# Power_MPU.net
KiCad netlist of a schematic drawn in Altium Designer
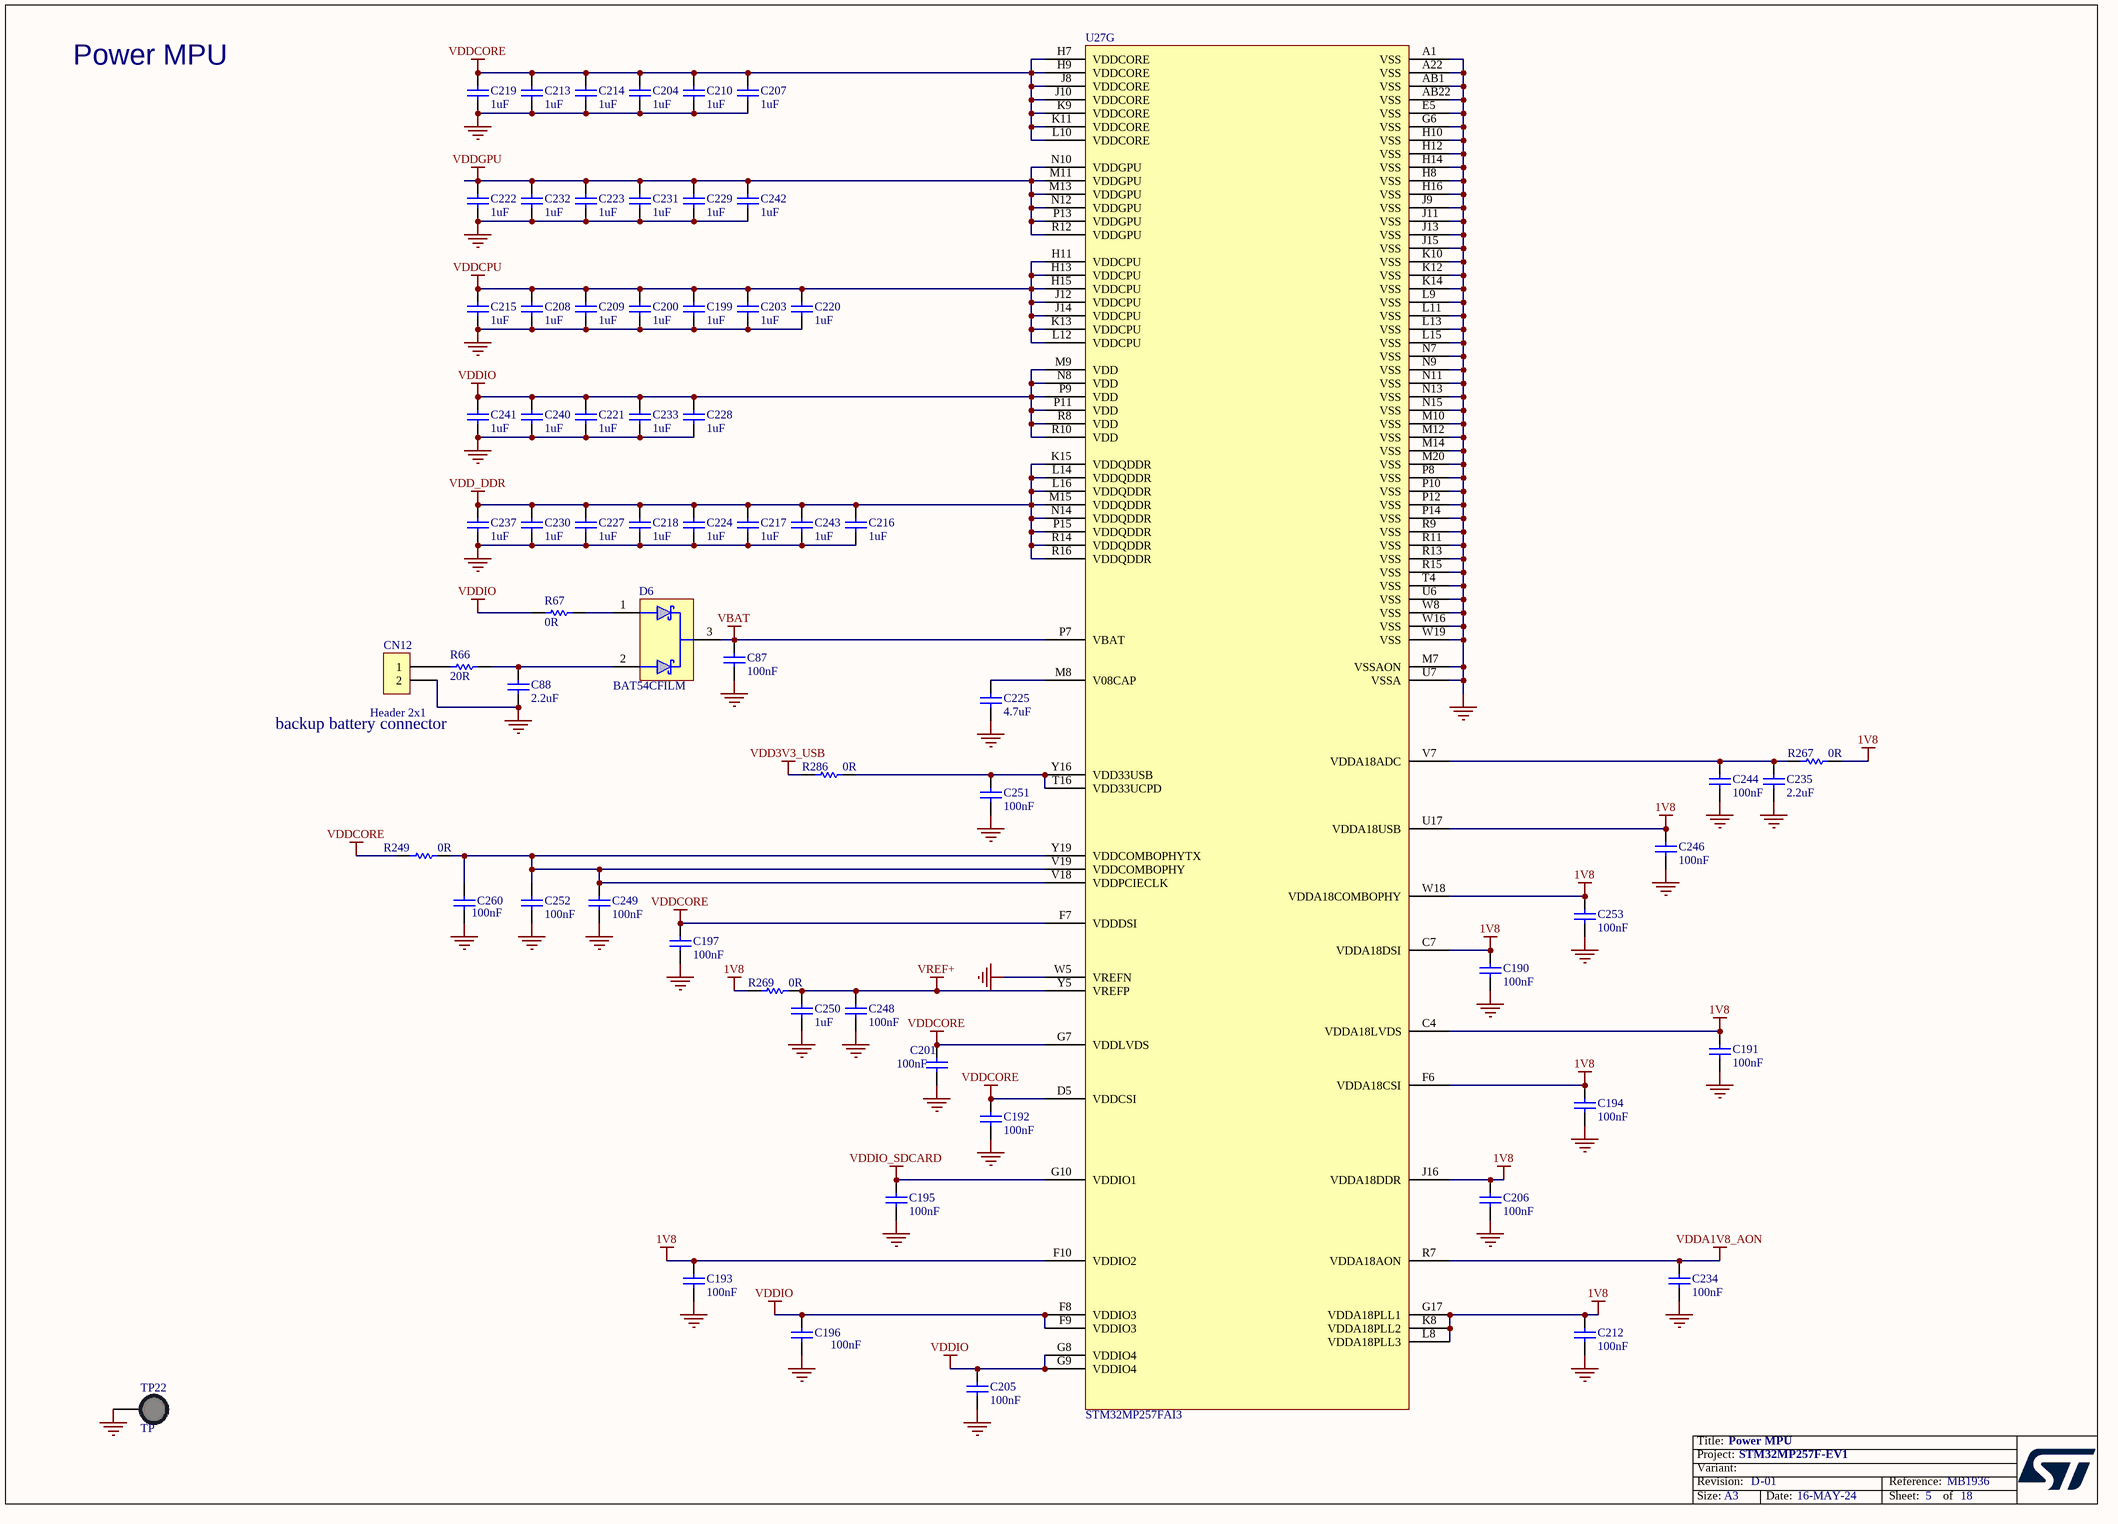
[diagram p0: Power_MPU.SchDoc]

(export (version "E")
  (design (tool "Eeschema 10.0.6"))
  (components
    (comp (ref "C87")
      (value "100nF")
      (footprint "MCD_PARTS:C0402")
      (description "Capacitor,100nF,16V,X7R,10%,0402")
      (fields
        (field (name "INTERNAL_PART_NUMBER") "MCD-00006")
        (field (name "MANUFACTURER_PART_NUMBER") "CC0402KRX7R7BB104")
        (field (name "PROVIDED_BY") "SUBCO")
      )
      (libsource (lib "MCD_PARTS_database") (part "Capacitor"))
    )
    (comp (ref "C88")
      (value "2.2uF")
      (footprint "MCD_PARTS:C0402")
      (description "Capacitor, MLCC, 2.2uF, 6V3, X5R,+/-10%, 0402, T=0.5mm")
      (fields (field (name "INTERNAL_PART_NUMBER") "MCD-01823") (field (name "MANUFACTURER") "MURATA"))
      (libsource (lib "MCD_PARTS_database") (part "Capacitor"))
    )
    (comp (ref "C190")
      (value "100nF")
      (footprint "MCD_PARTS:C0201_MURATA_GRM033_H0P3")
      (description "Capacitor, MLCC,100nF, 10V, X7R, +/-10%, 0201, T=0.3mm")
      (fields (field (name "INTERNAL_PART_NUMBER") "MCD-01535") (field (name "MANUFACTURER") "MURATA"))
      (libsource (lib "MCD_PARTS_database") (part "Capacitor"))
    )
    (comp (ref "C191")
      (value "100nF")
      (footprint "MCD_PARTS:C0201_MURATA_GRM033_H0P3")
      (description "Capacitor, MLCC,100nF, 10V, X7R, +/-10%, 0201, T=0.3mm")
      (fields (field (name "INTERNAL_PART_NUMBER") "MCD-01535") (field (name "MANUFACTURER") "MURATA"))
      (libsource (lib "MCD_PARTS_database") (part "Capacitor"))
    )
    (comp (ref "C192")
      (value "100nF")
      (footprint "MCD_PARTS:C0201_MURATA_GRM033_H0P3")
      (description "Capacitor, MLCC,100nF, 10V, X7R, +/-10%, 0201, T=0.3mm")
      (fields (field (name "INTERNAL_PART_NUMBER") "MCD-01535") (field (name "MANUFACTURER") "MURATA"))
      (libsource (lib "MCD_PARTS_database") (part "Capacitor"))
    )
    (comp (ref "C193")
      (value "100nF")
      (footprint "MCD_PARTS:C0201_MURATA_GRM033_H0P3")
      (description "Capacitor, MLCC,100nF, 10V, X7R, +/-10%, 0201, T=0.3mm")
      (fields (field (name "INTERNAL_PART_NUMBER") "MCD-01535") (field (name "MANUFACTURER") "MURATA"))
      (libsource (lib "MCD_PARTS_database") (part "Capacitor"))
    )
    (comp (ref "C194")
      (value "100nF")
      (footprint "MCD_PARTS:C0201_MURATA_GRM033_H0P3")
      (description "Capacitor, MLCC,100nF, 10V, X7R, +/-10%, 0201, T=0.3mm")
      (fields (field (name "INTERNAL_PART_NUMBER") "MCD-01535") (field (name "MANUFACTURER") "MURATA"))
      (libsource (lib "MCD_PARTS_database") (part "Capacitor"))
    )
    (comp (ref "C195")
      (value "100nF")
      (footprint "MCD_PARTS:C0201_MURATA_GRM033_H0P3")
      (description "Capacitor, MLCC,100nF, 10V, X7R, +/-10%, 0201, T=0.3mm")
      (fields (field (name "INTERNAL_PART_NUMBER") "MCD-01535") (field (name "MANUFACTURER") "MURATA"))
      (libsource (lib "MCD_PARTS_database") (part "Capacitor"))
    )
    (comp (ref "C196")
      (value "100nF")
      (footprint "MCD_PARTS:C0201_MURATA_GRM033_H0P3")
      (description "Capacitor, MLCC,100nF, 10V, X7R, +/-10%, 0201, T=0.3mm")
      (fields (field (name "INTERNAL_PART_NUMBER") "MCD-01535") (field (name "MANUFACTURER") "MURATA"))
      (libsource (lib "MCD_PARTS_database") (part "Capacitor"))
    )
    (comp (ref "C197")
      (value "100nF")
      (footprint "MCD_PARTS:C0201_MURATA_GRM033_H0P3")
      (description "Capacitor, MLCC,100nF, 10V, X7R, +/-10%, 0201, T=0.3mm")
      (fields (field (name "INTERNAL_PART_NUMBER") "MCD-01535") (field (name "MANUFACTURER") "MURATA"))
      (libsource (lib "MCD_PARTS_database") (part "Capacitor"))
    )
    (comp (ref "C199")
      (value "1uF")
      (footprint "MCD_PARTS:C0201_MURATA_GRM033_H0P3")
      (description "Capacitor, MLCC, 1uF, 6.3V, X5R, +/-20%, 0201, T=0,3mm")
      (fields
        (field (name "INTERNAL_PART_NUMBER") "MCD-02377")
        (field (name "MANUFACTURER_PART_NUMBER") "GRM033R60J105MEA2")
      )
      (libsource (lib "MCD_PARTS_database") (part "Capacitor"))
    )
    (comp (ref "C200")
      (value "1uF")
      (footprint "MCD_PARTS:C0201_MURATA_GRM033_H0P3")
      (description "Capacitor, MLCC, 1uF, 6.3V, X5R, +/-20%, 0201, T=0,3mm")
      (fields
        (field (name "INTERNAL_PART_NUMBER") "MCD-02377")
        (field (name "MANUFACTURER_PART_NUMBER") "GRM033R60J105MEA2")
      )
      (libsource (lib "MCD_PARTS_database") (part "Capacitor"))
    )
    (comp (ref "C201")
      (value "100nF")
      (footprint "MCD_PARTS:C0201_MURATA_GRM033_H0P3")
      (description "Capacitor, MLCC,100nF, 10V, X7R, +/-10%, 0201, T=0.3mm")
      (fields (field (name "INTERNAL_PART_NUMBER") "MCD-01535") (field (name "MANUFACTURER") "MURATA"))
      (libsource (lib "MCD_PARTS_database") (part "Capacitor"))
    )
    (comp (ref "C203")
      (value "1uF")
      (footprint "MCD_PARTS:C0201_MURATA_GRM033_H0P3")
      (description "Capacitor, MLCC, 1uF, 6.3V, X5R, +/-20%, 0201, T=0,3mm")
      (fields
        (field (name "INTERNAL_PART_NUMBER") "MCD-02377")
        (field (name "MANUFACTURER_PART_NUMBER") "GRM033R60J105MEA2")
      )
      (libsource (lib "MCD_PARTS_database") (part "Capacitor"))
    )
    (comp (ref "C204")
      (value "1uF")
      (footprint "MCD_PARTS:C0201_MURATA_GRM033_H0P3")
      (description "Capacitor, MLCC, 1uF, 6.3V, X5R, +/-20%, 0201, T=0,3mm")
      (fields
        (field (name "INTERNAL_PART_NUMBER") "MCD-02377")
        (field (name "MANUFACTURER_PART_NUMBER") "GRM033R60J105MEA2")
      )
      (libsource (lib "MCD_PARTS_database") (part "Capacitor"))
    )
    (comp (ref "C205")
      (value "100nF")
      (footprint "MCD_PARTS:C0201_MURATA_GRM033_H0P3")
      (description "Capacitor, MLCC,100nF, 10V, X7R, +/-10%, 0201, T=0.3mm")
      (fields (field (name "INTERNAL_PART_NUMBER") "MCD-01535") (field (name "MANUFACTURER") "MURATA"))
      (libsource (lib "MCD_PARTS_database") (part "Capacitor"))
    )
    (comp (ref "C206")
      (value "100nF")
      (footprint "MCD_PARTS:C0201_MURATA_GRM033_H0P3")
      (description "Capacitor, MLCC,100nF, 10V, X7R, +/-10%, 0201, T=0.3mm")
      (fields (field (name "INTERNAL_PART_NUMBER") "MCD-01535") (field (name "MANUFACTURER") "MURATA"))
      (libsource (lib "MCD_PARTS_database") (part "Capacitor"))
    )
    (comp (ref "C207")
      (value "1uF")
      (footprint "MCD_PARTS:C0201_MURATA_GRM033_H0P3")
      (description "Capacitor, MLCC, 1uF, 6.3V, X5R, +/-20%, 0201, T=0,3mm")
      (fields
        (field (name "INTERNAL_PART_NUMBER") "MCD-02377")
        (field (name "MANUFACTURER_PART_NUMBER") "GRM033R60J105MEA2")
      )
      (libsource (lib "MCD_PARTS_database") (part "Capacitor"))
    )
    (comp (ref "C208")
      (value "1uF")
      (footprint "MCD_PARTS:C0201_MURATA_GRM033_H0P3")
      (description "Capacitor, MLCC, 1uF, 6.3V, X5R, +/-20%, 0201, T=0,3mm")
      (fields
        (field (name "INTERNAL_PART_NUMBER") "MCD-02377")
        (field (name "MANUFACTURER_PART_NUMBER") "GRM033R60J105MEA2")
      )
      (libsource (lib "MCD_PARTS_database") (part "Capacitor"))
    )
    (comp (ref "C209")
      (value "1uF")
      (footprint "MCD_PARTS:C0201_MURATA_GRM033_H0P3")
      (description "Capacitor, MLCC, 1uF, 6.3V, X5R, +/-20%, 0201, T=0,3mm")
      (fields
        (field (name "INTERNAL_PART_NUMBER") "MCD-02377")
        (field (name "MANUFACTURER_PART_NUMBER") "GRM033R60J105MEA2")
      )
      (libsource (lib "MCD_PARTS_database") (part "Capacitor"))
    )
    (comp (ref "C210")
      (value "1uF")
      (footprint "MCD_PARTS:C0201_MURATA_GRM033_H0P3")
      (description "Capacitor, MLCC, 1uF, 6.3V, X5R, +/-20%, 0201, T=0,3mm")
      (fields
        (field (name "INTERNAL_PART_NUMBER") "MCD-02377")
        (field (name "MANUFACTURER_PART_NUMBER") "GRM033R60J105MEA2")
      )
      (libsource (lib "MCD_PARTS_database") (part "Capacitor"))
    )
    (comp (ref "C212")
      (value "100nF")
      (footprint "MCD_PARTS:C0201_MURATA_GRM033_H0P3")
      (description "Capacitor, MLCC,100nF, 10V, X7R, +/-10%, 0201, T=0.3mm")
      (fields (field (name "INTERNAL_PART_NUMBER") "MCD-01535") (field (name "MANUFACTURER") "MURATA"))
      (libsource (lib "MCD_PARTS_database") (part "Capacitor"))
    )
    (comp (ref "C213")
      (value "1uF")
      (footprint "MCD_PARTS:C0201_MURATA_GRM033_H0P3")
      (description "Capacitor, MLCC, 1uF, 6.3V, X5R, +/-20%, 0201, T=0,3mm")
      (fields
        (field (name "INTERNAL_PART_NUMBER") "MCD-02377")
        (field (name "MANUFACTURER_PART_NUMBER") "GRM033R60J105MEA2")
      )
      (libsource (lib "MCD_PARTS_database") (part "Capacitor"))
    )
    (comp (ref "C214")
      (value "1uF")
      (footprint "MCD_PARTS:C0201_MURATA_GRM033_H0P3")
      (description "Capacitor, MLCC, 1uF, 6.3V, X5R, +/-20%, 0201, T=0,3mm")
      (fields
        (field (name "INTERNAL_PART_NUMBER") "MCD-02377")
        (field (name "MANUFACTURER_PART_NUMBER") "GRM033R60J105MEA2")
      )
      (libsource (lib "MCD_PARTS_database") (part "Capacitor"))
    )
    (comp (ref "C215")
      (value "1uF")
      (footprint "MCD_PARTS:C0201_MURATA_GRM033_H0P3")
      (description "Capacitor, MLCC, 1uF, 6.3V, X5R, +/-20%, 0201, T=0,3mm")
      (fields
        (field (name "INTERNAL_PART_NUMBER") "MCD-02377")
        (field (name "MANUFACTURER_PART_NUMBER") "GRM033R60J105MEA2")
      )
      (libsource (lib "MCD_PARTS_database") (part "Capacitor"))
    )
    (comp (ref "C216")
      (value "1uF")
      (footprint "MCD_PARTS:C0201_MURATA_GRM033_H0P3")
      (description "Capacitor, MLCC, 1uF, 6.3V, X5R, +/-20%, 0201, T=0,3mm")
      (fields
        (field (name "INTERNAL_PART_NUMBER") "MCD-02377")
        (field (name "MANUFACTURER_PART_NUMBER") "GRM033R60J105MEA2")
      )
      (libsource (lib "MCD_PARTS_database") (part "Capacitor"))
    )
    (comp (ref "C217")
      (value "1uF")
      (footprint "MCD_PARTS:C0201_MURATA_GRM033_H0P3")
      (description "Capacitor, MLCC, 1uF, 6.3V, X5R, +/-20%, 0201, T=0,3mm")
      (fields
        (field (name "INTERNAL_PART_NUMBER") "MCD-02377")
        (field (name "MANUFACTURER_PART_NUMBER") "GRM033R60J105MEA2")
      )
      (libsource (lib "MCD_PARTS_database") (part "Capacitor"))
    )
    (comp (ref "C218")
      (value "1uF")
      (footprint "MCD_PARTS:C0201_MURATA_GRM033_H0P3")
      (description "Capacitor, MLCC, 1uF, 6.3V, X5R, +/-20%, 0201, T=0,3mm")
      (fields
        (field (name "INTERNAL_PART_NUMBER") "MCD-02377")
        (field (name "MANUFACTURER_PART_NUMBER") "GRM033R60J105MEA2")
      )
      (libsource (lib "MCD_PARTS_database") (part "Capacitor"))
    )
    (comp (ref "C219")
      (value "1uF")
      (footprint "MCD_PARTS:C0201_MURATA_GRM033_H0P3")
      (description "Capacitor, MLCC, 1uF, 6.3V, X5R, +/-20%, 0201, T=0,3mm")
      (fields
        (field (name "INTERNAL_PART_NUMBER") "MCD-02377")
        (field (name "MANUFACTURER_PART_NUMBER") "GRM033R60J105MEA2")
      )
      (libsource (lib "MCD_PARTS_database") (part "Capacitor"))
    )
    (comp (ref "C220")
      (value "1uF")
      (footprint "MCD_PARTS:C0201_MURATA_GRM033_H0P3")
      (description "Capacitor, MLCC, 1uF, 6.3V, X5R, +/-20%, 0201, T=0,3mm")
      (fields
        (field (name "INTERNAL_PART_NUMBER") "MCD-02377")
        (field (name "MANUFACTURER_PART_NUMBER") "GRM033R60J105MEA2")
      )
      (libsource (lib "MCD_PARTS_database") (part "Capacitor"))
    )
    (comp (ref "C221")
      (value "1uF")
      (footprint "MCD_PARTS:C0201_MURATA_GRM033_H0P3")
      (description "Capacitor, MLCC, 1uF, 6.3V, X5R, +/-20%, 0201, T=0,3mm")
      (fields
        (field (name "INTERNAL_PART_NUMBER") "MCD-02377")
        (field (name "MANUFACTURER_PART_NUMBER") "GRM033R60J105MEA2")
      )
      (libsource (lib "MCD_PARTS_database") (part "Capacitor"))
    )
    (comp (ref "C222")
      (value "1uF")
      (footprint "MCD_PARTS:C0201_MURATA_GRM033_H0P3")
      (description "Capacitor, MLCC, 1uF, 6.3V, X5R, +/-20%, 0201, T=0,3mm")
      (fields
        (field (name "INTERNAL_PART_NUMBER") "MCD-02377")
        (field (name "MANUFACTURER_PART_NUMBER") "GRM033R60J105MEA2")
      )
      (libsource (lib "MCD_PARTS_database") (part "Capacitor"))
    )
    (comp (ref "C223")
      (value "1uF")
      (footprint "MCD_PARTS:C0201_MURATA_GRM033_H0P3")
      (description "Capacitor, MLCC, 1uF, 6.3V, X5R, +/-20%, 0201, T=0,3mm")
      (fields
        (field (name "INTERNAL_PART_NUMBER") "MCD-02377")
        (field (name "MANUFACTURER_PART_NUMBER") "GRM033R60J105MEA2")
      )
      (libsource (lib "MCD_PARTS_database") (part "Capacitor"))
    )
    (comp (ref "C224")
      (value "1uF")
      (footprint "MCD_PARTS:C0201_MURATA_GRM033_H0P3")
      (description "Capacitor, MLCC, 1uF, 6.3V, X5R, +/-20%, 0201, T=0,3mm")
      (fields
        (field (name "INTERNAL_PART_NUMBER") "MCD-02377")
        (field (name "MANUFACTURER_PART_NUMBER") "GRM033R60J105MEA2")
      )
      (libsource (lib "MCD_PARTS_database") (part "Capacitor"))
    )
    (comp (ref "C225")
      (value "4.7uF")
      (footprint "MCD_PARTS:C0201_H0P5")
      (description "Capacitor, MLCC, 4,7uF, 6V3, X5R, +/-20%, 0201, T=0.5mm")
      (fields (field (name "INTERNAL_PART_NUMBER") "MCD-01534") (field (name "MANUFACTURER") "MURATA"))
      (libsource (lib "MCD_PARTS_database") (part "Capacitor"))
    )
    (comp (ref "C227")
      (value "1uF")
      (footprint "MCD_PARTS:C0201_MURATA_GRM033_H0P3")
      (description "Capacitor, MLCC, 1uF, 6.3V, X5R, +/-20%, 0201, T=0,3mm")
      (fields
        (field (name "INTERNAL_PART_NUMBER") "MCD-02377")
        (field (name "MANUFACTURER_PART_NUMBER") "GRM033R60J105MEA2")
      )
      (libsource (lib "MCD_PARTS_database") (part "Capacitor"))
    )
    (comp (ref "C228")
      (value "1uF")
      (footprint "MCD_PARTS:C0201_MURATA_GRM033_H0P3")
      (description "Capacitor, MLCC, 1uF, 6.3V, X5R, +/-20%, 0201, T=0,3mm")
      (fields
        (field (name "INTERNAL_PART_NUMBER") "MCD-02377")
        (field (name "MANUFACTURER_PART_NUMBER") "GRM033R60J105MEA2")
      )
      (libsource (lib "MCD_PARTS_database") (part "Capacitor"))
    )
    (comp (ref "C229")
      (value "1uF")
      (footprint "MCD_PARTS:C0201_MURATA_GRM033_H0P3")
      (description "Capacitor, MLCC, 1uF, 6.3V, X5R, +/-20%, 0201, T=0,3mm")
      (fields
        (field (name "INTERNAL_PART_NUMBER") "MCD-02377")
        (field (name "MANUFACTURER_PART_NUMBER") "GRM033R60J105MEA2")
      )
      (libsource (lib "MCD_PARTS_database") (part "Capacitor"))
    )
    (comp (ref "C230")
      (value "1uF")
      (footprint "MCD_PARTS:C0201_MURATA_GRM033_H0P3")
      (description "Capacitor, MLCC, 1uF, 6.3V, X5R, +/-20%, 0201, T=0,3mm")
      (fields
        (field (name "INTERNAL_PART_NUMBER") "MCD-02377")
        (field (name "MANUFACTURER_PART_NUMBER") "GRM033R60J105MEA2")
      )
      (libsource (lib "MCD_PARTS_database") (part "Capacitor"))
    )
    (comp (ref "C231")
      (value "1uF")
      (footprint "MCD_PARTS:C0201_MURATA_GRM033_H0P3")
      (description "Capacitor, MLCC, 1uF, 6.3V, X5R, +/-20%, 0201, T=0,3mm")
      (fields
        (field (name "INTERNAL_PART_NUMBER") "MCD-02377")
        (field (name "MANUFACTURER_PART_NUMBER") "GRM033R60J105MEA2")
      )
      (libsource (lib "MCD_PARTS_database") (part "Capacitor"))
    )
    (comp (ref "C232")
      (value "1uF")
      (footprint "MCD_PARTS:C0201_MURATA_GRM033_H0P3")
      (description "Capacitor, MLCC, 1uF, 6.3V, X5R, +/-20%, 0201, T=0,3mm")
      (fields
        (field (name "INTERNAL_PART_NUMBER") "MCD-02377")
        (field (name "MANUFACTURER_PART_NUMBER") "GRM033R60J105MEA2")
      )
      (libsource (lib "MCD_PARTS_database") (part "Capacitor"))
    )
    (comp (ref "C233")
      (value "1uF")
      (footprint "MCD_PARTS:C0201_MURATA_GRM033_H0P3")
      (description "Capacitor, MLCC, 1uF, 6.3V, X5R, +/-20%, 0201, T=0,3mm")
      (fields
        (field (name "INTERNAL_PART_NUMBER") "MCD-02377")
        (field (name "MANUFACTURER_PART_NUMBER") "GRM033R60J105MEA2")
      )
      (libsource (lib "MCD_PARTS_database") (part "Capacitor"))
    )
    (comp (ref "C234")
      (value "100nF")
      (footprint "MCD_PARTS:C0201_MURATA_GRM033_H0P3")
      (description "Capacitor, MLCC,100nF, 10V, X7R, +/-10%, 0201, T=0.3mm")
      (fields (field (name "INTERNAL_PART_NUMBER") "MCD-01535") (field (name "MANUFACTURER") "MURATA"))
      (libsource (lib "MCD_PARTS_database") (part "Capacitor"))
    )
    (comp (ref "C235")
      (value "2.2uF")
      (footprint "MCD_PARTS:C0201_H0P5")
      (description "Capacitor, MLCC, 2.2uF, 10V, X5R,+/-10%, 0201, T=0.5mm")
      (fields (field (name "INTERNAL_PART_NUMBER") "MCD-02235") (field (name "MANUFACTURER") "MURATA"))
      (libsource (lib "MCD_PARTS_database") (part "Capacitor"))
    )
    (comp (ref "C237")
      (value "1uF")
      (footprint "MCD_PARTS:C0201_MURATA_GRM033_H0P3")
      (description "Capacitor, MLCC, 1uF, 6.3V, X5R, +/-20%, 0201, T=0,3mm")
      (fields
        (field (name "INTERNAL_PART_NUMBER") "MCD-02377")
        (field (name "MANUFACTURER_PART_NUMBER") "GRM033R60J105MEA2")
      )
      (libsource (lib "MCD_PARTS_database") (part "Capacitor"))
    )
    (comp (ref "C240")
      (value "1uF")
      (footprint "MCD_PARTS:C0201_MURATA_GRM033_H0P3")
      (description "Capacitor, MLCC, 1uF, 6.3V, X5R, +/-20%, 0201, T=0,3mm")
      (fields
        (field (name "INTERNAL_PART_NUMBER") "MCD-02377")
        (field (name "MANUFACTURER_PART_NUMBER") "GRM033R60J105MEA2")
      )
      (libsource (lib "MCD_PARTS_database") (part "Capacitor"))
    )
    (comp (ref "C241")
      (value "1uF")
      (footprint "MCD_PARTS:C0201_MURATA_GRM033_H0P3")
      (description "Capacitor, MLCC, 1uF, 6.3V, X5R, +/-20%, 0201, T=0,3mm")
      (fields
        (field (name "INTERNAL_PART_NUMBER") "MCD-02377")
        (field (name "MANUFACTURER_PART_NUMBER") "GRM033R60J105MEA2")
      )
      (libsource (lib "MCD_PARTS_database") (part "Capacitor"))
    )
    (comp (ref "C242")
      (value "1uF")
      (footprint "MCD_PARTS:C0201_MURATA_GRM033_H0P3")
      (description "Capacitor, MLCC, 1uF, 6.3V, X5R, +/-20%, 0201, T=0,3mm")
      (fields
        (field (name "INTERNAL_PART_NUMBER") "MCD-02377")
        (field (name "MANUFACTURER_PART_NUMBER") "GRM033R60J105MEA2")
      )
      (libsource (lib "MCD_PARTS_database") (part "Capacitor"))
    )
    (comp (ref "C243")
      (value "1uF")
      (footprint "MCD_PARTS:C0201_MURATA_GRM033_H0P3")
      (description "Capacitor, MLCC, 1uF, 6.3V, X5R, +/-20%, 0201, T=0,3mm")
      (fields
        (field (name "INTERNAL_PART_NUMBER") "MCD-02377")
        (field (name "MANUFACTURER_PART_NUMBER") "GRM033R60J105MEA2")
      )
      (libsource (lib "MCD_PARTS_database") (part "Capacitor"))
    )
    (comp (ref "C244")
      (value "100nF")
      (footprint "MCD_PARTS:C0201_MURATA_GRM033_H0P3")
      (description "Capacitor, MLCC,100nF, 10V, X7R, +/-10%, 0201, T=0.3mm")
      (fields (field (name "INTERNAL_PART_NUMBER") "MCD-01535") (field (name "MANUFACTURER") "MURATA"))
      (libsource (lib "MCD_PARTS_database") (part "Capacitor"))
    )
    (comp (ref "C246")
      (value "100nF")
      (footprint "MCD_PARTS:C0201_MURATA_GRM033_H0P3")
      (description "Capacitor, MLCC,100nF, 10V, X7R, +/-10%, 0201, T=0.3mm")
      (fields (field (name "INTERNAL_PART_NUMBER") "MCD-01535") (field (name "MANUFACTURER") "MURATA"))
      (libsource (lib "MCD_PARTS_database") (part "Capacitor"))
    )
    (comp (ref "C248")
      (value "100nF")
      (footprint "MCD_PARTS:C0201_MURATA_GRM033_H0P3")
      (description "Capacitor, MLCC,100nF, 10V, X7R, +/-10%, 0201, T=0.3mm")
      (fields (field (name "INTERNAL_PART_NUMBER") "MCD-01535") (field (name "MANUFACTURER") "MURATA"))
      (libsource (lib "MCD_PARTS_database") (part "Capacitor"))
    )
    (comp (ref "C249")
      (value "100nF")
      (footprint "MCD_PARTS:C0201_MURATA_GRM033_H0P3")
      (description "Capacitor, MLCC,100nF, 10V, X7R, +/-10%, 0201, T=0.3mm")
      (fields (field (name "INTERNAL_PART_NUMBER") "MCD-01535") (field (name "MANUFACTURER") "MURATA"))
      (libsource (lib "MCD_PARTS_database") (part "Capacitor"))
    )
    (comp (ref "C250")
      (value "1uF")
      (footprint "MCD_PARTS:C0201_MURATA_GRM033_H0P3")
      (description "Capacitor, MLCC, 1uF, 6.3V, X5R, +/-20%, 0201, T=0,3mm")
      (fields
        (field (name "INTERNAL_PART_NUMBER") "MCD-02377")
        (field (name "MANUFACTURER_PART_NUMBER") "GRM033R60J105MEA2")
      )
      (libsource (lib "MCD_PARTS_database") (part "Capacitor"))
    )
    (comp (ref "C251")
      (value "100nF")
      (footprint "MCD_PARTS:C0201_MURATA_GRM033_H0P3")
      (description "Capacitor, MLCC,100nF, 10V, X7R, +/-10%, 0201, T=0.3mm")
      (fields (field (name "INTERNAL_PART_NUMBER") "MCD-01535") (field (name "MANUFACTURER") "MURATA"))
      (libsource (lib "MCD_PARTS_database") (part "Capacitor"))
    )
    (comp (ref "C252")
      (value "100nF")
      (footprint "MCD_PARTS:C0201_MURATA_GRM033_H0P3")
      (description "Capacitor, MLCC,100nF, 10V, X7R, +/-10%, 0201, T=0.3mm")
      (fields (field (name "INTERNAL_PART_NUMBER") "MCD-01535") (field (name "MANUFACTURER") "MURATA"))
      (libsource (lib "MCD_PARTS_database") (part "Capacitor"))
    )
    (comp (ref "C253")
      (value "100nF")
      (footprint "MCD_PARTS:C0201_MURATA_GRM033_H0P3")
      (description "Capacitor, MLCC,100nF, 10V, X7R, +/-10%, 0201, T=0.3mm")
      (fields (field (name "INTERNAL_PART_NUMBER") "MCD-01535") (field (name "MANUFACTURER") "MURATA"))
      (libsource (lib "MCD_PARTS_database") (part "Capacitor"))
    )
    (comp (ref "C260")
      (value "100nF")
      (footprint "MCD_PARTS:C0201_MURATA_GRM033_H0P3")
      (description "Capacitor, MLCC,100nF, 10V, X7R, +/-10%, 0201, T=0.3mm")
      (fields (field (name "INTERNAL_PART_NUMBER") "MCD-01535") (field (name "MANUFACTURER") "MURATA"))
      (libsource (lib "MCD_PARTS_database") (part "Capacitor"))
    )
    (comp (ref "CN12")
      (value "Header 2x1")
      (footprint "MCD_PARTS:CON_MOLEX_53047-0210")
      (description "Header 2 circuits, 1.25mm Pitch ,  Vertical, with Friction Lock")
      (fields
        (field (name "INTERNAL_PART_NUMBER") "MCD-00655")
        (field (name "MANUFACTURER_PART_NUMBER") "53047-0210")
        (field (name "PROVIDED_BY") "SUBCO")
      )
      (libsource (lib "MCD_PARTS_database") (part "Header 2x1"))
    )
    (comp (ref "D6")
      (value "BAT54CFILM")
      (footprint "MCD_PARTS:DIO_SOT23")
      (description "Diode, Schottky, Dual Common Cathode, 0V3, 300mA, 40V, SOT-23")
      (fields
        (field (name "INTERNAL_PART_NUMBER") "MCD-03280")
        (field (name "MANUFACTURER") "STMICROELECTRONICS")
      )
      (libsource (lib "MCD_PARTS_database") (part "DIODE_3P_DUAL_COMMON_CATHODE"))
    )
    (comp (ref "R66")
      (value "20R")
      (footprint "MCD_PARTS:R0402")
      (description "Resistor, 20R, 0402, +/-1%, 1/16W")
      (fields (field (name "INTERNAL_PART_NUMBER") "MCD-00058") (field (name "BMS_PART_NUMBER") "9131027"))
      (libsource (lib "MCD_PARTS_database") (part "Resistor"))
    )
    (comp (ref "R67")
      (value "0R")
      (footprint "MCD_PARTS:R0402")
      (description "Resistor, 0R, 0402, +/-5%, 1/16W")
      (fields
        (field (name "INTERNAL_PART_NUMBER") "MCD-00052")
        (field (name "MANUFACTURER_PART_NUMBER") "RC0402JR-070RL")
      )
      (libsource (lib "MCD_PARTS_database") (part "Resistor"))
    )
    (comp (ref "R249")
      (value "0R")
      (footprint "MCD_PARTS:R0603")
      (description "Resistor, 0R, 0603, +/-5%, 1/10W")
      (fields (field (name "INTERNAL_PART_NUMBER") "MCD-00056") (field (name "MANUFACTURER") "YAGEO"))
      (libsource (lib "MCD_PARTS_database") (part "Resistor"))
    )
    (comp (ref "R267")
      (value "0R")
      (footprint "MCD_PARTS:R0402")
      (description "Resistor,0R,0402,5%,1/16W")
      (fields
        (field (name "INTERNAL_PART_NUMBER") "MCD-00052")
        (field (name "MANUFACTURER_PART_NUMBER") "RC0402JR-070RL")
        (field (name "PROVIDED_BY") "SUBCO")
      )
      (libsource (lib "MCD_PARTS_database") (part "Resistor"))
    )
    (comp (ref "R269")
      (value "0R")
      (footprint "MCD_PARTS:R0402")
      (description "Resistor,0R,0402,5%,1/16W")
      (fields
        (field (name "INTERNAL_PART_NUMBER") "MCD-00052")
        (field (name "MANUFACTURER_PART_NUMBER") "RC0402JR-070RL")
        (field (name "PROVIDED_BY") "SUBCO")
      )
      (libsource (lib "MCD_PARTS_database") (part "Resistor"))
    )
    (comp (ref "R286")
      (value "0R")
      (footprint "MCD_PARTS:R0402")
      (description "Resistor,0R,0402,5%,1/16W")
      (fields
        (field (name "INTERNAL_PART_NUMBER") "MCD-00052")
        (field (name "MANUFACTURER_PART_NUMBER") "RC0402JR-070RL")
        (field (name "PROVIDED_BY") "SUBCO")
      )
      (libsource (lib "MCD_PARTS_database") (part "Resistor"))
    )
    (comp (ref "TP22")
      (value "TP")
      (footprint "MCD_PARTS:TP_PTH-1P02MM_TEST-TERMINAL_RS_101-2391_BLACK")
      (description "Vero Technologies 1.02mm Black Terminal Post")
      (fields
        (field (name "INTERNAL_PART_NUMBER") "MCD-00713")
        (field (name "MANUFACTURER_PART_NUMBER") "20-2137")
        (field (name "PROVIDED_BY") "SUBCO")
      )
      (libsource (lib "MCD_PARTS_database") (part "Test_pin_conn_black"))
    )
    (comp (ref "U27")
      (value "STM32MP257FAI3")
      (footprint "ICC_LFBGA436_18X18_P080_H1P70_STM32MP257_CODE-B0D1")
      (description "MPU, ARM Cortex-A35 + M33 32-bit MPU, 808KB RAM, With Crypto")
      (fields
        (field (name "INTERNAL_PART_NUMBER") "MCD-02000")
        (field (name "MANUFACTURER") "STMICROELECTRONICS")
      )
      (libsource (lib "MCD_PARTS_database") (part "STM32MP257FAI3"))
    )
  )
  (nets
    (net (code "1") (name "1V8") (class "Default")
      (node (ref "C190") (pin "2") (pinfunction "2_2") (pintype "passive"))
      (node (ref "C191") (pin "2") (pinfunction "2_2") (pintype "passive"))
      (node (ref "C193") (pin "2") (pinfunction "2_2") (pintype "passive"))
      (node (ref "C194") (pin "2") (pinfunction "2_2") (pintype "passive"))
      (node (ref "C206") (pin "2") (pinfunction "2_2") (pintype "passive"))
      (node (ref "C212") (pin "2") (pinfunction "2_2") (pintype "passive"))
      (node (ref "C246") (pin "2") (pinfunction "2_2") (pintype "passive"))
      (node (ref "C253") (pin "2") (pinfunction "2_2") (pintype "passive"))
      (node (ref "R267") (pin "2") (pinfunction "2_2") (pintype "passive"))
      (node (ref "R269") (pin "1") (pinfunction "1_1") (pintype "passive"))
      (node (ref "U27") (pin "C4") (pinfunction "VDDA18LVDS_C4") (pintype "passive"))
      (node (ref "U27") (pin "C7") (pinfunction "VDDA18DSI_C7") (pintype "passive"))
      (node (ref "U27") (pin "F10") (pinfunction "VDDIO2_F10") (pintype "passive"))
      (node (ref "U27") (pin "F6") (pinfunction "VDDA18CSI_F6") (pintype "passive"))
      (node (ref "U27") (pin "G17") (pinfunction "VDDA18PLL1_G17") (pintype "passive"))
      (node (ref "U27") (pin "J16") (pinfunction "VDDA18DDR_J16") (pintype "passive"))
      (node (ref "U27") (pin "K8") (pinfunction "VDDA18PLL2_K8") (pintype "passive"))
      (node (ref "U27") (pin "L8") (pinfunction "VDDA18PLL3_L8") (pintype "passive"))
      (node (ref "U27") (pin "U17") (pinfunction "VDDA18USB_U17") (pintype "passive"))
      (node (ref "U27") (pin "W18") (pinfunction "VDDA18COMBOPHY_W18") (pintype "passive"))
    )
    (net (code "2") (name "GND") (class "Default")
      (node (ref "C190") (pin "1") (pinfunction "1_1") (pintype "passive"))
      (node (ref "C191") (pin "1") (pinfunction "1_1") (pintype "passive"))
      (node (ref "C192") (pin "1") (pinfunction "1_1") (pintype "passive"))
      (node (ref "C193") (pin "1") (pinfunction "1_1") (pintype "passive"))
      (node (ref "C194") (pin "1") (pinfunction "1_1") (pintype "passive"))
      (node (ref "C195") (pin "1") (pinfunction "1_1") (pintype "passive"))
      (node (ref "C196") (pin "1") (pinfunction "1_1") (pintype "passive"))
      (node (ref "C197") (pin "1") (pinfunction "1_1") (pintype "passive"))
      (node (ref "C199") (pin "1") (pinfunction "1_1") (pintype "passive"))
      (node (ref "C200") (pin "2") (pinfunction "2_2") (pintype "passive"))
      (node (ref "C201") (pin "1") (pinfunction "1_1") (pintype "passive"))
      (node (ref "C203") (pin "1") (pinfunction "1_1") (pintype "passive"))
      (node (ref "C204") (pin "2") (pinfunction "2_2") (pintype "passive"))
      (node (ref "C205") (pin "1") (pinfunction "1_1") (pintype "passive"))
      (node (ref "C206") (pin "1") (pinfunction "1_1") (pintype "passive"))
      (node (ref "C207") (pin "1") (pinfunction "1_1") (pintype "passive"))
      (node (ref "C208") (pin "1") (pinfunction "1_1") (pintype "passive"))
      (node (ref "C209") (pin "1") (pinfunction "1_1") (pintype "passive"))
      (node (ref "C210") (pin "1") (pinfunction "1_1") (pintype "passive"))
      (node (ref "C212") (pin "1") (pinfunction "1_1") (pintype "passive"))
      (node (ref "C213") (pin "1") (pinfunction "1_1") (pintype "passive"))
      (node (ref "C214") (pin "1") (pinfunction "1_1") (pintype "passive"))
      (node (ref "C215") (pin "2") (pinfunction "2_2") (pintype "passive"))
      (node (ref "C216") (pin "1") (pinfunction "1_1") (pintype "passive"))
      (node (ref "C217") (pin "1") (pinfunction "1_1") (pintype "passive"))
      (node (ref "C218") (pin "1") (pinfunction "1_1") (pintype "passive"))
      (node (ref "C219") (pin "2") (pinfunction "2_2") (pintype "passive"))
      (node (ref "C220") (pin "1") (pinfunction "1_1") (pintype "passive"))
      (node (ref "C221") (pin "1") (pinfunction "1_1") (pintype "passive"))
      (node (ref "C222") (pin "1") (pinfunction "1_1") (pintype "passive"))
      (node (ref "C223") (pin "1") (pinfunction "1_1") (pintype "passive"))
      (node (ref "C224") (pin "1") (pinfunction "1_1") (pintype "passive"))
      (node (ref "C225") (pin "1") (pinfunction "1_1") (pintype "passive"))
      (node (ref "C227") (pin "1") (pinfunction "1_1") (pintype "passive"))
      (node (ref "C228") (pin "1") (pinfunction "1_1") (pintype "passive"))
      (node (ref "C229") (pin "2") (pinfunction "2_2") (pintype "passive"))
      (node (ref "C230") (pin "2") (pinfunction "2_2") (pintype "passive"))
      (node (ref "C231") (pin "1") (pinfunction "1_1") (pintype "passive"))
      (node (ref "C232") (pin "1") (pinfunction "1_1") (pintype "passive"))
      (node (ref "C233") (pin "2") (pinfunction "2_2") (pintype "passive"))
      (node (ref "C234") (pin "1") (pinfunction "1_1") (pintype "passive"))
      (node (ref "C235") (pin "1") (pinfunction "1_1") (pintype "passive"))
      (node (ref "C237") (pin "1") (pinfunction "1_1") (pintype "passive"))
      (node (ref "C240") (pin "1") (pinfunction "1_1") (pintype "passive"))
      (node (ref "C241") (pin "2") (pinfunction "2_2") (pintype "passive"))
      (node (ref "C242") (pin "1") (pinfunction "1_1") (pintype "passive"))
      (node (ref "C243") (pin "1") (pinfunction "1_1") (pintype "passive"))
      (node (ref "C244") (pin "1") (pinfunction "1_1") (pintype "passive"))
      (node (ref "C246") (pin "1") (pinfunction "1_1") (pintype "passive"))
      (node (ref "C248") (pin "1") (pinfunction "1_1") (pintype "passive"))
      (node (ref "C249") (pin "1") (pinfunction "1_1") (pintype "passive"))
      (node (ref "C250") (pin "1") (pinfunction "1_1") (pintype "passive"))
      (node (ref "C251") (pin "1") (pinfunction "1_1") (pintype "passive"))
      (node (ref "C252") (pin "1") (pinfunction "1_1") (pintype "passive"))
      (node (ref "C253") (pin "1") (pinfunction "1_1") (pintype "passive"))
      (node (ref "C260") (pin "1") (pinfunction "1_1") (pintype "passive"))
      (node (ref "C87") (pin "1") (pinfunction "1_1") (pintype "passive"))
      (node (ref "C88") (pin "1") (pinfunction "1_1") (pintype "passive"))
      (node (ref "CN12") (pin "2") (pinfunction "2_2") (pintype "passive"))
      (node (ref "TP22") (pin "1") (pinfunction "1_1") (pintype "passive"))
      (node (ref "U27") (pin "A1") (pinfunction "VSS_A1") (pintype "passive"))
      (node (ref "U27") (pin "A22") (pinfunction "VSS_A22") (pintype "passive"))
      (node (ref "U27") (pin "AB1") (pinfunction "VSS_AB1") (pintype "passive"))
      (node (ref "U27") (pin "AB22") (pinfunction "VSS_AB22") (pintype "passive"))
      (node (ref "U27") (pin "E5") (pinfunction "VSS_E5") (pintype "passive"))
      (node (ref "U27") (pin "G6") (pinfunction "VSS_G6") (pintype "passive"))
      (node (ref "U27") (pin "H10") (pinfunction "VSS_H10") (pintype "passive"))
      (node (ref "U27") (pin "H12") (pinfunction "VSS_H12") (pintype "passive"))
      (node (ref "U27") (pin "H14") (pinfunction "VSS_H14") (pintype "passive"))
      (node (ref "U27") (pin "H16") (pinfunction "VSS_H16") (pintype "passive"))
      (node (ref "U27") (pin "H8") (pinfunction "VSS_H8") (pintype "passive"))
      (node (ref "U27") (pin "J11") (pinfunction "VSS_J11") (pintype "passive"))
      (node (ref "U27") (pin "J13") (pinfunction "VSS_J13") (pintype "passive"))
      (node (ref "U27") (pin "J15") (pinfunction "VSS_J15") (pintype "passive"))
      (node (ref "U27") (pin "J9") (pinfunction "VSS_J9") (pintype "passive"))
      (node (ref "U27") (pin "K10") (pinfunction "VSS_K10") (pintype "passive"))
      (node (ref "U27") (pin "K12") (pinfunction "VSS_K12") (pintype "passive"))
      (node (ref "U27") (pin "K14") (pinfunction "VSS_K14") (pintype "passive"))
      (node (ref "U27") (pin "L11") (pinfunction "VSS_L11") (pintype "passive"))
      (node (ref "U27") (pin "L13") (pinfunction "VSS_L13") (pintype "passive"))
      (node (ref "U27") (pin "L15") (pinfunction "VSS_L15") (pintype "passive"))
      (node (ref "U27") (pin "L9") (pinfunction "VSS_L9") (pintype "passive"))
      (node (ref "U27") (pin "M10") (pinfunction "VSS_M10") (pintype "passive"))
      (node (ref "U27") (pin "M12") (pinfunction "VSS_M12") (pintype "passive"))
      (node (ref "U27") (pin "M14") (pinfunction "VSS_M14") (pintype "passive"))
      (node (ref "U27") (pin "M20") (pinfunction "VSS_M20") (pintype "passive"))
      (node (ref "U27") (pin "M7") (pinfunction "VSSAON_M7") (pintype "passive"))
      (node (ref "U27") (pin "N11") (pinfunction "VSS_N11") (pintype "passive"))
      (node (ref "U27") (pin "N13") (pinfunction "VSS_N13") (pintype "passive"))
      (node (ref "U27") (pin "N15") (pinfunction "VSS_N15") (pintype "passive"))
      (node (ref "U27") (pin "N7") (pinfunction "VSS_N7") (pintype "passive"))
      (node (ref "U27") (pin "N9") (pinfunction "VSS_N9") (pintype "passive"))
      (node (ref "U27") (pin "P10") (pinfunction "VSS_P10") (pintype "passive"))
      (node (ref "U27") (pin "P12") (pinfunction "VSS_P12") (pintype "passive"))
      (node (ref "U27") (pin "P14") (pinfunction "VSS_P14") (pintype "passive"))
      (node (ref "U27") (pin "P8") (pinfunction "VSS_P8") (pintype "passive"))
      (node (ref "U27") (pin "R11") (pinfunction "VSS_R11") (pintype "passive"))
      (node (ref "U27") (pin "R13") (pinfunction "VSS_R13") (pintype "passive"))
      (node (ref "U27") (pin "R15") (pinfunction "VSS_R15") (pintype "passive"))
      (node (ref "U27") (pin "R9") (pinfunction "VSS_R9") (pintype "passive"))
      (node (ref "U27") (pin "T4") (pinfunction "VSS_T4") (pintype "passive"))
      (node (ref "U27") (pin "U6") (pinfunction "VSS_U6") (pintype "passive"))
      (node (ref "U27") (pin "U7") (pinfunction "VSSA_U7") (pintype "passive"))
      (node (ref "U27") (pin "W16") (pinfunction "VSS_W16") (pintype "passive"))
      (node (ref "U27") (pin "W19") (pinfunction "VSS_W19") (pintype "passive"))
      (node (ref "U27") (pin "W5") (pinfunction "VREFN_W5") (pintype "passive"))
      (node (ref "U27") (pin "W8") (pinfunction "VSS_W8") (pintype "passive"))
    )
    (net (code "3") (name "Net-(C88-Pad2)") (class "Default")
      (node (ref "C88") (pin "2") (pinfunction "2_2") (pintype "passive"))
      (node (ref "D6") (pin "2") (pinfunction "2_2") (pintype "passive"))
      (node (ref "R66") (pin "2") (pinfunction "2_2") (pintype "passive"))
    )
    (net (code "4") (name "Net-(CN12-Pad1)") (class "Default")
      (node (ref "CN12") (pin "1") (pinfunction "1_1") (pintype "passive"))
      (node (ref "R66") (pin "1") (pinfunction "1_1") (pintype "passive"))
    )
    (net (code "5") (name "Net-(D6-Pad1)") (class "Default")
      (node (ref "D6") (pin "1") (pinfunction "1_1") (pintype "passive"))
      (node (ref "R67") (pin "1") (pinfunction "1_1") (pintype "passive"))
    )
    (net (code "6") (name "Net-(U27G-V08CAP)") (class "Default")
      (node (ref "C225") (pin "2") (pinfunction "2_2") (pintype "passive"))
      (node (ref "U27") (pin "M8") (pinfunction "V08CAP_M8") (pintype "passive"))
    )
    (net (code "7") (name "Net-(U27G-VDD33UCPD)") (class "Default")
      (node (ref "C251") (pin "2") (pinfunction "2_2") (pintype "passive"))
      (node (ref "R286") (pin "2") (pinfunction "2_2") (pintype "passive"))
      (node (ref "U27") (pin "T16") (pinfunction "VDD33UCPD_T16") (pintype "passive"))
      (node (ref "U27") (pin "Y16") (pinfunction "VDD33USB_Y16") (pintype "passive"))
    )
    (net (code "8") (name "Net-(U27G-VDDA18ADC)") (class "Default")
      (node (ref "C235") (pin "2") (pinfunction "2_2") (pintype "passive"))
      (node (ref "C244") (pin "2") (pinfunction "2_2") (pintype "passive"))
      (node (ref "R267") (pin "1") (pinfunction "1_1") (pintype "passive"))
      (node (ref "U27") (pin "V7") (pinfunction "VDDA18ADC_V7") (pintype "passive"))
    )
    (net (code "9") (name "Net-(U27G-VDDCOMBOPHY)") (class "Default")
      (node (ref "C249") (pin "2") (pinfunction "2_2") (pintype "passive"))
      (node (ref "C252") (pin "2") (pinfunction "2_2") (pintype "passive"))
      (node (ref "C260") (pin "2") (pinfunction "2_2") (pintype "passive"))
      (node (ref "R249") (pin "2") (pinfunction "2_2") (pintype "passive"))
      (node (ref "U27") (pin "V18") (pinfunction "VDDPCIECLK_V18") (pintype "passive"))
      (node (ref "U27") (pin "V19") (pinfunction "VDDCOMBOPHY_V19") (pintype "passive"))
      (node (ref "U27") (pin "Y19") (pinfunction "VDDCOMBOPHYTX_Y19") (pintype "passive"))
    )
    (net (code "10") (name "VBAT") (class "Default")
      (node (ref "C87") (pin "2") (pinfunction "2_2") (pintype "passive"))
      (node (ref "D6") (pin "3") (pinfunction "3_3") (pintype "passive"))
      (node (ref "U27") (pin "P7") (pinfunction "VBAT_P7") (pintype "passive"))
    )
    (net (code "11") (name "VDD3V3_USB") (class "Default")
      (node (ref "R286") (pin "1") (pinfunction "1_1") (pintype "passive"))
    )
    (net (code "12") (name "VDDA1V8_AON") (class "Default")
      (node (ref "C234") (pin "2") (pinfunction "2_2") (pintype "passive"))
      (node (ref "U27") (pin "R7") (pinfunction "VDDA18AON_R7") (pintype "passive"))
    )
    (net (code "13") (name "VDDCORE") (class "Default")
      (node (ref "C192") (pin "2") (pinfunction "2_2") (pintype "passive"))
      (node (ref "C197") (pin "2") (pinfunction "2_2") (pintype "passive"))
      (node (ref "C201") (pin "2") (pinfunction "2_2") (pintype "passive"))
      (node (ref "C204") (pin "1") (pinfunction "1_1") (pintype "passive"))
      (node (ref "C207") (pin "2") (pinfunction "2_2") (pintype "passive"))
      (node (ref "C210") (pin "2") (pinfunction "2_2") (pintype "passive"))
      (node (ref "C213") (pin "2") (pinfunction "2_2") (pintype "passive"))
      (node (ref "C214") (pin "2") (pinfunction "2_2") (pintype "passive"))
      (node (ref "C219") (pin "1") (pinfunction "1_1") (pintype "passive"))
      (node (ref "R249") (pin "1") (pinfunction "1_1") (pintype "passive"))
      (node (ref "U27") (pin "D5") (pinfunction "VDDCSI_D5") (pintype "passive"))
      (node (ref "U27") (pin "F7") (pinfunction "VDDDSI_F7") (pintype "passive"))
      (node (ref "U27") (pin "G7") (pinfunction "VDDLVDS_G7") (pintype "passive"))
      (node (ref "U27") (pin "H7") (pinfunction "VDDCORE_H7") (pintype "passive"))
      (node (ref "U27") (pin "H9") (pinfunction "VDDCORE_H9") (pintype "passive"))
      (node (ref "U27") (pin "J10") (pinfunction "VDDCORE_J10") (pintype "passive"))
      (node (ref "U27") (pin "J8") (pinfunction "VDDCORE_J8") (pintype "passive"))
      (node (ref "U27") (pin "K11") (pinfunction "VDDCORE_K11") (pintype "passive"))
      (node (ref "U27") (pin "K9") (pinfunction "VDDCORE_K9") (pintype "passive"))
      (node (ref "U27") (pin "L10") (pinfunction "VDDCORE_L10") (pintype "passive"))
    )
    (net (code "14") (name "VDDCPU") (class "Default")
      (node (ref "C199") (pin "2") (pinfunction "2_2") (pintype "passive"))
      (node (ref "C200") (pin "1") (pinfunction "1_1") (pintype "passive"))
      (node (ref "C203") (pin "2") (pinfunction "2_2") (pintype "passive"))
      (node (ref "C208") (pin "2") (pinfunction "2_2") (pintype "passive"))
      (node (ref "C209") (pin "2") (pinfunction "2_2") (pintype "passive"))
      (node (ref "C215") (pin "1") (pinfunction "1_1") (pintype "passive"))
      (node (ref "C220") (pin "2") (pinfunction "2_2") (pintype "passive"))
      (node (ref "U27") (pin "H11") (pinfunction "VDDCPU_H11") (pintype "passive"))
      (node (ref "U27") (pin "H13") (pinfunction "VDDCPU_H13") (pintype "passive"))
      (node (ref "U27") (pin "H15") (pinfunction "VDDCPU_H15") (pintype "passive"))
      (node (ref "U27") (pin "J12") (pinfunction "VDDCPU_J12") (pintype "passive"))
      (node (ref "U27") (pin "J14") (pinfunction "VDDCPU_J14") (pintype "passive"))
      (node (ref "U27") (pin "K13") (pinfunction "VDDCPU_K13") (pintype "passive"))
      (node (ref "U27") (pin "L12") (pinfunction "VDDCPU_L12") (pintype "passive"))
    )
    (net (code "15") (name "VDDGPU") (class "Default")
      (node (ref "C222") (pin "2") (pinfunction "2_2") (pintype "passive"))
      (node (ref "C223") (pin "2") (pinfunction "2_2") (pintype "passive"))
      (node (ref "C229") (pin "1") (pinfunction "1_1") (pintype "passive"))
      (node (ref "C231") (pin "2") (pinfunction "2_2") (pintype "passive"))
      (node (ref "C232") (pin "2") (pinfunction "2_2") (pintype "passive"))
      (node (ref "C242") (pin "2") (pinfunction "2_2") (pintype "passive"))
      (node (ref "U27") (pin "M11") (pinfunction "VDDGPU_M11") (pintype "passive"))
      (node (ref "U27") (pin "M13") (pinfunction "VDDGPU_M13") (pintype "passive"))
      (node (ref "U27") (pin "N10") (pinfunction "VDDGPU_N10") (pintype "passive"))
      (node (ref "U27") (pin "N12") (pinfunction "VDDGPU_N12") (pintype "passive"))
      (node (ref "U27") (pin "P13") (pinfunction "VDDGPU_P13") (pintype "passive"))
      (node (ref "U27") (pin "R12") (pinfunction "VDDGPU_R12") (pintype "passive"))
    )
    (net (code "16") (name "VDDIO") (class "Default")
      (node (ref "C196") (pin "2") (pinfunction "2_2") (pintype "passive"))
      (node (ref "C205") (pin "2") (pinfunction "2_2") (pintype "passive"))
      (node (ref "C221") (pin "2") (pinfunction "2_2") (pintype "passive"))
      (node (ref "C228") (pin "2") (pinfunction "2_2") (pintype "passive"))
      (node (ref "C233") (pin "1") (pinfunction "1_1") (pintype "passive"))
      (node (ref "C240") (pin "2") (pinfunction "2_2") (pintype "passive"))
      (node (ref "C241") (pin "1") (pinfunction "1_1") (pintype "passive"))
      (node (ref "R67") (pin "2") (pinfunction "2_2") (pintype "passive"))
      (node (ref "U27") (pin "F8") (pinfunction "VDDIO3_F8") (pintype "passive"))
      (node (ref "U27") (pin "F9") (pinfunction "VDDIO3_F9") (pintype "passive"))
      (node (ref "U27") (pin "G8") (pinfunction "VDDIO4_G8") (pintype "passive"))
      (node (ref "U27") (pin "G9") (pinfunction "VDDIO4_G9") (pintype "passive"))
      (node (ref "U27") (pin "M9") (pinfunction "VDD_M9") (pintype "passive"))
      (node (ref "U27") (pin "N8") (pinfunction "VDD_N8") (pintype "passive"))
      (node (ref "U27") (pin "P11") (pinfunction "VDD_P11") (pintype "passive"))
      (node (ref "U27") (pin "P9") (pinfunction "VDD_P9") (pintype "passive"))
      (node (ref "U27") (pin "R10") (pinfunction "VDD_R10") (pintype "passive"))
      (node (ref "U27") (pin "R8") (pinfunction "VDD_R8") (pintype "passive"))
    )
    (net (code "17") (name "VDDIO_SDCARD") (class "Default")
      (node (ref "C195") (pin "2") (pinfunction "2_2") (pintype "passive"))
      (node (ref "U27") (pin "G10") (pinfunction "VDDIO1_G10") (pintype "passive"))
    )
    (net (code "18") (name "VDD_DDR") (class "Default")
      (node (ref "C216") (pin "2") (pinfunction "2_2") (pintype "passive"))
      (node (ref "C217") (pin "2") (pinfunction "2_2") (pintype "passive"))
      (node (ref "C218") (pin "2") (pinfunction "2_2") (pintype "passive"))
      (node (ref "C224") (pin "2") (pinfunction "2_2") (pintype "passive"))
      (node (ref "C227") (pin "2") (pinfunction "2_2") (pintype "passive"))
      (node (ref "C230") (pin "1") (pinfunction "1_1") (pintype "passive"))
      (node (ref "C237") (pin "2") (pinfunction "2_2") (pintype "passive"))
      (node (ref "C243") (pin "2") (pinfunction "2_2") (pintype "passive"))
      (node (ref "U27") (pin "K15") (pinfunction "VDDQDDR_K15") (pintype "passive"))
      (node (ref "U27") (pin "L14") (pinfunction "VDDQDDR_L14") (pintype "passive"))
      (node (ref "U27") (pin "L16") (pinfunction "VDDQDDR_L16") (pintype "passive"))
      (node (ref "U27") (pin "M15") (pinfunction "VDDQDDR_M15") (pintype "passive"))
      (node (ref "U27") (pin "N14") (pinfunction "VDDQDDR_N14") (pintype "passive"))
      (node (ref "U27") (pin "P15") (pinfunction "VDDQDDR_P15") (pintype "passive"))
      (node (ref "U27") (pin "R14") (pinfunction "VDDQDDR_R14") (pintype "passive"))
      (node (ref "U27") (pin "R16") (pinfunction "VDDQDDR_R16") (pintype "passive"))
    )
    (net (code "19") (name "VREF+") (class "Default")
      (node (ref "C248") (pin "2") (pinfunction "2_2") (pintype "passive"))
      (node (ref "C250") (pin "2") (pinfunction "2_2") (pintype "passive"))
      (node (ref "R269") (pin "2") (pinfunction "2_2") (pintype "passive"))
      (node (ref "U27") (pin "Y5") (pinfunction "VREFP_Y5") (pintype "passive"))
    )
  )
)
